# esp_slavev2.net
KiCad netlist of a schematic drawn in Altium Designer
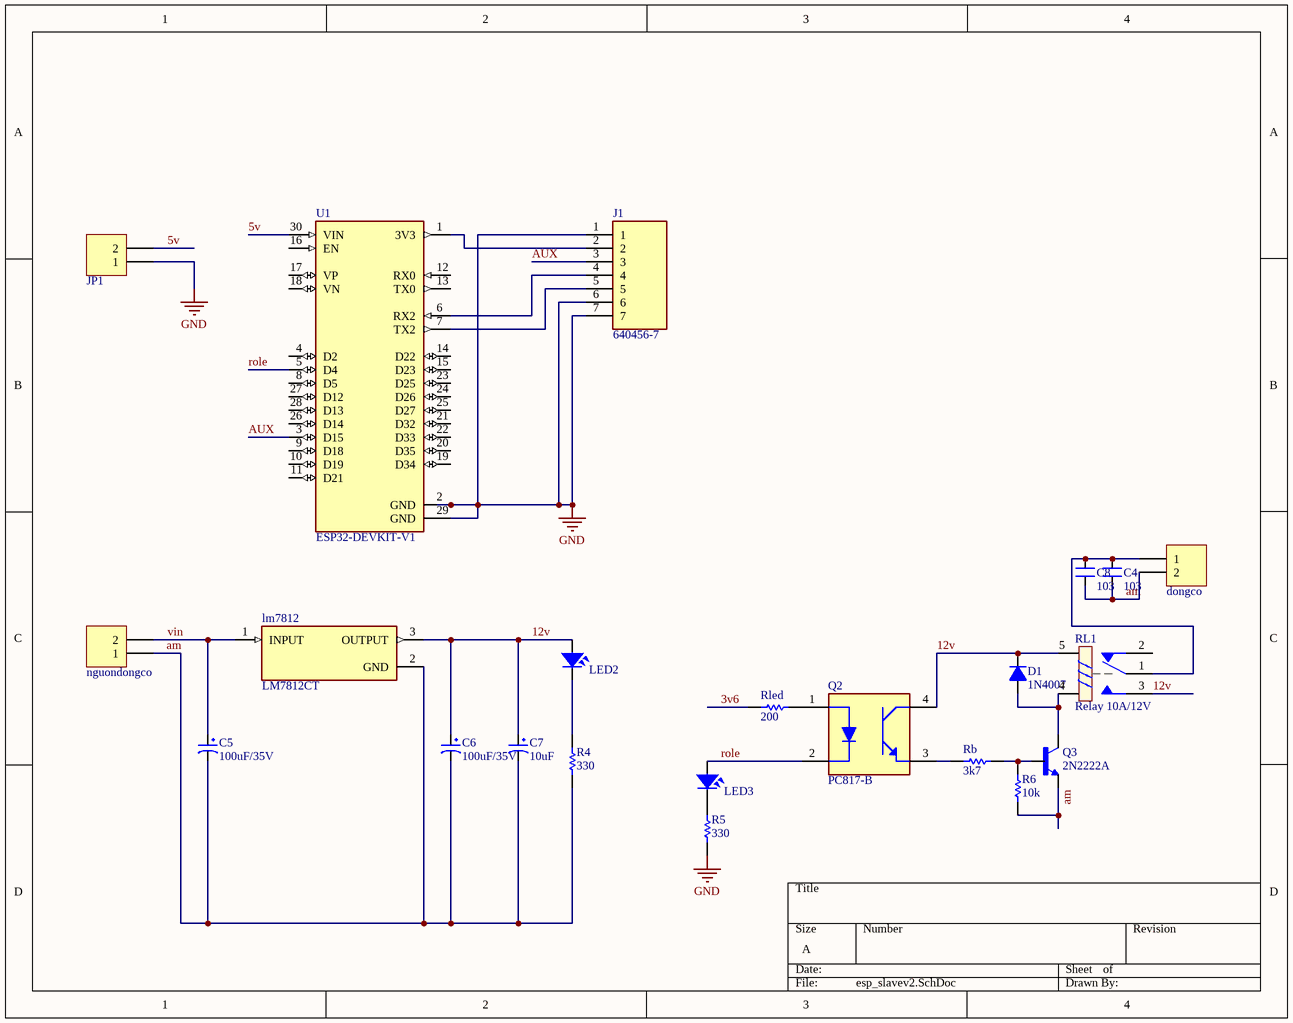
[diagram p0: esp_slavev2.SchDoc]

(export (version "E")
  (design (tool "Eeschema 10.0.6"))
  (components
    (comp (ref "C4")
      (value "103")
      (footprint "CN1.5")
      (description "Cap np 682pF => 104pF")
      (libsource (lib "syhaunguyen") (part "CN1.5"))
    )
    (comp (ref "C5")
      (value "100uF/35V")
      (footprint "CP1.5/3.4")
      (description "Cap 100uF/35V - 470uF/16V")
      (libsource (lib "syhaunguyen") (part "CP3"))
    )
    (comp (ref "C6")
      (value "100uF/35V")
      (footprint "CP1.5/3.4")
      (description "Cap 100uF/35V - 470uF/16V")
      (libsource (lib "syhaunguyen") (part "CP3"))
    )
    (comp (ref "C7")
      (value "10uF")
      (footprint "CP1/2")
      (description "Cap P  0,1uF < 22uF , 16 - 50V")
      (libsource (lib "syhaunguyen") (part "CP1"))
    )
    (comp (ref "C8")
      (value "103")
      (footprint "CN1.5")
      (description "Cap np 682pF => 104pF")
      (libsource (lib "syhaunguyen") (part "CN1.5"))
    )
    (comp (ref "D1")
      (value "1N4007")
      (footprint "D1A")
      (description "Diode 1A")
      (libsource (lib "syhaunguyen") (part "D1A"))
    )
    (comp (ref "dongco")
      (value "Header 2_1")
      (footprint "HED2")
      (description "Header, 2-Pin")
      (fields (field (name "MANUFACTURER") "Generic Components"))
      (libsource (lib "syhaunguyen") (part "Header 2_1"))
    )
    (comp (ref "J1")
      (value "640456-7")
      (footprint "TE_640456-7")
      (description "Header Friction Lock MTA-100 7 250 VAC Polyester Tin Copper Alloy Tin ¦ TE Connectivity 640456-7")
      (fields (field (name "MF") "TE Connectivity"))
      (libsource (lib "640456-7") (part "640456-7"))
    )
    (comp (ref "JP1")
      (value "Header 2_1")
      (footprint "HED2")
      (description "Header, 2-Pin")
      (fields (field (name "MANUFACTURER") "Generic Components"))
      (libsource (lib "") (part "Header 2_1_1"))
    )
    (comp (ref "LED2")
      (value "LED")
      (footprint "LED-3")
      (description "LED Single colour Green and Red")
      (libsource (lib "syhaunguyen") (part "LED"))
    )
    (comp (ref "LED3")
      (value "LED")
      (footprint "LED-3")
      (description "LED Single colour Green and Red")
      (libsource (lib "syhaunguyen") (part "LED"))
    )
    (comp (ref "lm7812")
      (value "LM7812CT")
      (footprint "TO253P1057X470X2040-3")
      (description "Linear Voltage Regulator IC Positive Fixed 1 Output 1A TO-220-3")
      (fields (field (name "MF") "ON Semiconductor"))
      (libsource (lib "LM7812CT") (part "LM7812CT"))
    )
    (comp (ref "nguondongco")
      (value "Header 2_1")
      (footprint "HED2")
      (description "Header, 2-Pin")
      (fields (field (name "MANUFACTURER") "Generic Components"))
      (libsource (lib "") (part "Header 2_1_1"))
    )
    (comp (ref "Q2")
      (value "PC817-B")
      (footprint "DIP762W50P254L650H455Q4B")
      (description "Phototransistors 4-DIP (0.300, 7.62mm)")
      (fields (field (name "MF") "American Bright"))
      (libsource (lib "PC817-B") (part "PC817-B"))
    )
    (comp (ref "Q3")
      (value "2N2222A")
      (footprint "TO92254P470H750-3")
      (description "BJT, TO-92, 40V, 600mA, NPN, 0.625W, 150Â°C")
      (fields (field (name "MF") "Diotec Semiconductor"))
      (libsource (lib "2N2222A") (part "2N2222A"))
    )
    (comp (ref "R4")
      (value "330")
      (footprint "R1/4W")
      (description "Resistor")
      (fields
        (field (name "MANUFACTURER") "Generic Components")
        (field (name "Comment") "Res1")
        (field (name "PUBLISHER") "Altium Hobart Technology Centre")
      )
      (libsource (lib "syhaunguyen") (part "Res1_4"))
    )
    (comp (ref "R5")
      (value "330")
      (footprint "R1/4W")
      (description "Resistor")
      (fields
        (field (name "MANUFACTURER") "Generic Components")
        (field (name "Comment") "Res1")
        (field (name "PUBLISHER") "Altium Hobart Technology Centre")
      )
      (libsource (lib "syhaunguyen") (part "Res1_4"))
    )
    (comp (ref "R6")
      (value "10k")
      (footprint "R1/4W")
      (description "Resistor")
      (fields
        (field (name "MANUFACTURER") "Generic Components")
        (field (name "Comment") "Res1")
        (field (name "PUBLISHER") "Altium Hobart Technology Centre")
      )
      (libsource (lib "syhaunguyen") (part "Res1_4"))
    )
    (comp (ref "Rb")
      (value "3k7")
      (footprint "R1/4W")
      (description "Resistor")
      (fields
        (field (name "MANUFACTURER") "Generic Components")
        (field (name "Comment") "Res1")
        (field (name "PUBLISHER") "Altium Hobart Technology Centre")
      )
      (libsource (lib "syhaunguyen") (part "Res1_4"))
    )
    (comp (ref "RL1")
      (value "Relay 10A/12V")
      (footprint "RL_SPDT_10A")
      (description "Relay SPDT,10A - 12VDC 5 Pin")
      (libsource (lib "syhaunguyen") (part "Relay 1"))
    )
    (comp (ref "Rled")
      (value "200")
      (footprint "R1/4W")
      (description "Resistor")
      (fields
        (field (name "MANUFACTURER") "Generic Components")
        (field (name "Comment") "Res1")
        (field (name "PUBLISHER") "Altium Hobart Technology Centre")
      )
      (libsource (lib "syhaunguyen") (part "Res1_4"))
    )
    (comp (ref "U1")
      (value "ESP32-DEVKIT-V1")
      (footprint "MODULE_ESP32_DEVKIT_V1")
      (fields (field (name "MF") "Do it"))
      (libsource (lib "ESP32-DEVKIT-V1") (part "ESP32-DEVKIT-V1"))
    )
  )
  (nets
    (net (code "1") (name "/3v6") (class "Default")
      (node (ref "Rled") (pin "1") (pinfunction "1_1") (pintype "passive"))
    )
    (net (code "2") (name "/5v") (class "Default")
      (node (ref "JP1") (pin "2") (pinfunction "2_2") (pintype "passive"))
      (node (ref "U1") (pin "30") (pinfunction "VIN_30") (pintype "input"))
    )
    (net (code "3") (name "/12v") (class "Default")
      (node (ref "C6") (pin "1") (pinfunction "1_1") (pintype "passive"))
      (node (ref "C7") (pin "1") (pinfunction "1_1") (pintype "passive"))
      (node (ref "D1") (pin "2") (pinfunction "K_2") (pintype "passive"))
      (node (ref "LED2") (pin "1") (pinfunction "1_1") (pintype "passive"))
      (node (ref "Q2") (pin "4") (pinfunction "COLLECTOR_4") (pintype "passive"))
      (node (ref "RL1") (pin "3") (pinfunction "3_3") (pintype "passive"))
      (node (ref "RL1") (pin "5") (pinfunction "5_5") (pintype "passive"))
      (node (ref "lm7812") (pin "3") (pinfunction "OUTPUT_3") (pintype "output"))
    )
    (net (code "4") (name "/AUX") (class "Default")
      (node (ref "J1") (pin "3") (pinfunction "3_3") (pintype "passive"))
      (node (ref "U1") (pin "3") (pinfunction "D15_3") (pintype "bidirectional"))
    )
    (net (code "5") (name "/am") (class "Default")
      (node (ref "C4") (pin "1") (pinfunction "1_1") (pintype "passive"))
      (node (ref "C5") (pin "2") (pinfunction "2_2") (pintype "passive"))
      (node (ref "C6") (pin "2") (pinfunction "2_2") (pintype "passive"))
      (node (ref "C7") (pin "2") (pinfunction "2_2") (pintype "passive"))
      (node (ref "C8") (pin "1") (pinfunction "1_1") (pintype "passive"))
      (node (ref "Q3") (pin "1") (pinfunction "E_1") (pintype "passive"))
      (node (ref "R4") (pin "2") (pinfunction "2_2") (pintype "passive"))
      (node (ref "R6") (pin "1") (pinfunction "1_1") (pintype "passive"))
      (node (ref "dongco") (pin "2") (pinfunction "2_2") (pintype "passive"))
      (node (ref "lm7812") (pin "2") (pinfunction "GND_2") (pintype "power_in"))
      (node (ref "nguondongco") (pin "1") (pinfunction "1_1") (pintype "passive"))
    )
    (net (code "6") (name "/role") (class "Default")
      (node (ref "LED3") (pin "1") (pinfunction "1_1") (pintype "passive"))
      (node (ref "Q2") (pin "2") (pinfunction "CATHODE_2") (pintype "passive"))
      (node (ref "U1") (pin "5") (pinfunction "D4_5") (pintype "bidirectional"))
    )
    (net (code "7") (name "/vin") (class "Default")
      (node (ref "C5") (pin "1") (pinfunction "1_1") (pintype "passive"))
      (node (ref "lm7812") (pin "1") (pinfunction "INPUT_1") (pintype "input"))
      (node (ref "nguondongco") (pin "2") (pinfunction "2_2") (pintype "passive"))
    )
    (net (code "8") (name "GND") (class "Default")
      (node (ref "J1") (pin "1") (pinfunction "1_1") (pintype "passive"))
      (node (ref "J1") (pin "6") (pinfunction "6_6") (pintype "passive"))
      (node (ref "J1") (pin "7") (pinfunction "7_7") (pintype "passive"))
      (node (ref "JP1") (pin "1") (pinfunction "1_1") (pintype "passive"))
      (node (ref "R5") (pin "2") (pinfunction "2_2") (pintype "passive"))
      (node (ref "U1") (pin "2") (pinfunction "GND_2") (pintype "power_in"))
      (node (ref "U1") (pin "29") (pinfunction "GND_29") (pintype "power_in"))
    )
    (net (code "9") (name "Net-(C4-Pad2)") (class "Default")
      (node (ref "C4") (pin "2") (pinfunction "2_2") (pintype "passive"))
      (node (ref "C8") (pin "2") (pinfunction "2_2") (pintype "passive"))
      (node (ref "RL1") (pin "1") (pinfunction "1_1") (pintype "passive"))
      (node (ref "dongco") (pin "1") (pinfunction "1_1") (pintype "passive"))
    )
    (net (code "10") (name "Net-(D1-A)") (class "Default")
      (node (ref "D1") (pin "1") (pinfunction "A_1") (pintype "passive"))
      (node (ref "Q3") (pin "3") (pinfunction "C_3") (pintype "passive"))
      (node (ref "RL1") (pin "4") (pinfunction "4_4") (pintype "passive"))
    )
    (net (code "11") (name "Net-(LED2-Pad2)") (class "Default")
      (node (ref "LED2") (pin "2") (pinfunction "2_2") (pintype "passive"))
      (node (ref "R4") (pin "1") (pinfunction "1_1") (pintype "passive"))
    )
    (net (code "12") (name "Net-(LED3-Pad2)") (class "Default")
      (node (ref "LED3") (pin "2") (pinfunction "2_2") (pintype "passive"))
      (node (ref "R5") (pin "1") (pinfunction "1_1") (pintype "passive"))
    )
    (net (code "13") (name "Net-(Q2-ANODE)") (class "Default")
      (node (ref "Q2") (pin "1") (pinfunction "ANODE_1") (pintype "passive"))
      (node (ref "Rled") (pin "2") (pinfunction "2_2") (pintype "passive"))
    )
    (net (code "14") (name "Net-(Q2-EMITTER)") (class "Default")
      (node (ref "Q2") (pin "3") (pinfunction "EMITTER_3") (pintype "passive"))
      (node (ref "Rb") (pin "1") (pinfunction "1_1") (pintype "passive"))
    )
    (net (code "15") (name "Net-(Q3-B)") (class "Default")
      (node (ref "Q3") (pin "2") (pinfunction "B_2") (pintype "passive"))
      (node (ref "R6") (pin "2") (pinfunction "2_2") (pintype "passive"))
      (node (ref "Rb") (pin "2") (pinfunction "2_2") (pintype "passive"))
    )
    (net (code "16") (name "Net-(U1-3V3)") (class "Default")
      (node (ref "J1") (pin "2") (pinfunction "2_2") (pintype "passive"))
      (node (ref "U1") (pin "1") (pinfunction "3V3_1") (pintype "output"))
    )
    (net (code "17") (name "Net-(U1-RX2)") (class "Default")
      (node (ref "J1") (pin "4") (pinfunction "4_4") (pintype "passive"))
      (node (ref "U1") (pin "6") (pinfunction "RX2_6") (pintype "input"))
    )
    (net (code "18") (name "Net-(U1-TX2)") (class "Default")
      (node (ref "J1") (pin "5") (pinfunction "5_5") (pintype "passive"))
      (node (ref "U1") (pin "7") (pinfunction "TX2_7") (pintype "output"))
    )
    (net (code "19") (name "unconnected-(RL1-Pad2)") (class "Default")
      (node (ref "RL1") (pin "2") (pinfunction "2_2") (pintype "passive"))
    )
    (net (code "20") (name "unconnected-(U1-D2-Pad4)") (class "Default")
      (node (ref "U1") (pin "4") (pinfunction "D2_4") (pintype "bidirectional"))
    )
    (net (code "21") (name "unconnected-(U1-D5-Pad8)") (class "Default")
      (node (ref "U1") (pin "8") (pinfunction "D5_8") (pintype "bidirectional"))
    )
    (net (code "22") (name "unconnected-(U1-D12-Pad27)") (class "Default")
      (node (ref "U1") (pin "27") (pinfunction "D12_27") (pintype "bidirectional"))
    )
    (net (code "23") (name "unconnected-(U1-D13-Pad28)") (class "Default")
      (node (ref "U1") (pin "28") (pinfunction "D13_28") (pintype "bidirectional"))
    )
    (net (code "24") (name "unconnected-(U1-D14-Pad26)") (class "Default")
      (node (ref "U1") (pin "26") (pinfunction "D14_26") (pintype "bidirectional"))
    )
    (net (code "25") (name "unconnected-(U1-D18-Pad9)") (class "Default")
      (node (ref "U1") (pin "9") (pinfunction "D18_9") (pintype "bidirectional"))
    )
    (net (code "26") (name "unconnected-(U1-D19-Pad10)") (class "Default")
      (node (ref "U1") (pin "10") (pinfunction "D19_10") (pintype "bidirectional"))
    )
    (net (code "27") (name "unconnected-(U1-D21-Pad11)") (class "Default")
      (node (ref "U1") (pin "11") (pinfunction "D21_11") (pintype "bidirectional"))
    )
    (net (code "28") (name "unconnected-(U1-D22-Pad14)") (class "Default")
      (node (ref "U1") (pin "14") (pinfunction "D22_14") (pintype "bidirectional"))
    )
    (net (code "29") (name "unconnected-(U1-D23-Pad15)") (class "Default")
      (node (ref "U1") (pin "15") (pinfunction "D23_15") (pintype "bidirectional"))
    )
    (net (code "30") (name "unconnected-(U1-D25-Pad23)") (class "Default")
      (node (ref "U1") (pin "23") (pinfunction "D25_23") (pintype "bidirectional"))
    )
    (net (code "31") (name "unconnected-(U1-D26-Pad24)") (class "Default")
      (node (ref "U1") (pin "24") (pinfunction "D26_24") (pintype "bidirectional"))
    )
    (net (code "32") (name "unconnected-(U1-D27-Pad25)") (class "Default")
      (node (ref "U1") (pin "25") (pinfunction "D27_25") (pintype "bidirectional"))
    )
    (net (code "33") (name "unconnected-(U1-D32-Pad21)") (class "Default")
      (node (ref "U1") (pin "21") (pinfunction "D32_21") (pintype "bidirectional"))
    )
    (net (code "34") (name "unconnected-(U1-D33-Pad22)") (class "Default")
      (node (ref "U1") (pin "22") (pinfunction "D33_22") (pintype "bidirectional"))
    )
    (net (code "35") (name "unconnected-(U1-D34-Pad19)") (class "Default")
      (node (ref "U1") (pin "19") (pinfunction "D34_19") (pintype "bidirectional"))
    )
    (net (code "36") (name "unconnected-(U1-D35-Pad20)") (class "Default")
      (node (ref "U1") (pin "20") (pinfunction "D35_20") (pintype "bidirectional"))
    )
    (net (code "37") (name "unconnected-(U1-EN-Pad16)") (class "Default")
      (node (ref "U1") (pin "16") (pinfunction "EN_16") (pintype "input"))
    )
    (net (code "38") (name "unconnected-(U1-RX0-Pad12)") (class "Default")
      (node (ref "U1") (pin "12") (pinfunction "RX0_12") (pintype "input"))
    )
    (net (code "39") (name "unconnected-(U1-TX0-Pad13)") (class "Default")
      (node (ref "U1") (pin "13") (pinfunction "TX0_13") (pintype "output"))
    )
    (net (code "40") (name "unconnected-(U1-VN-Pad18)") (class "Default")
      (node (ref "U1") (pin "18") (pinfunction "VN_18") (pintype "bidirectional"))
    )
    (net (code "41") (name "unconnected-(U1-VP-Pad17)") (class "Default")
      (node (ref "U1") (pin "17") (pinfunction "VP_17") (pintype "bidirectional"))
    )
  )
)
